# Solenoid_15.net
KiCad netlist of a schematic drawn in EAGLE
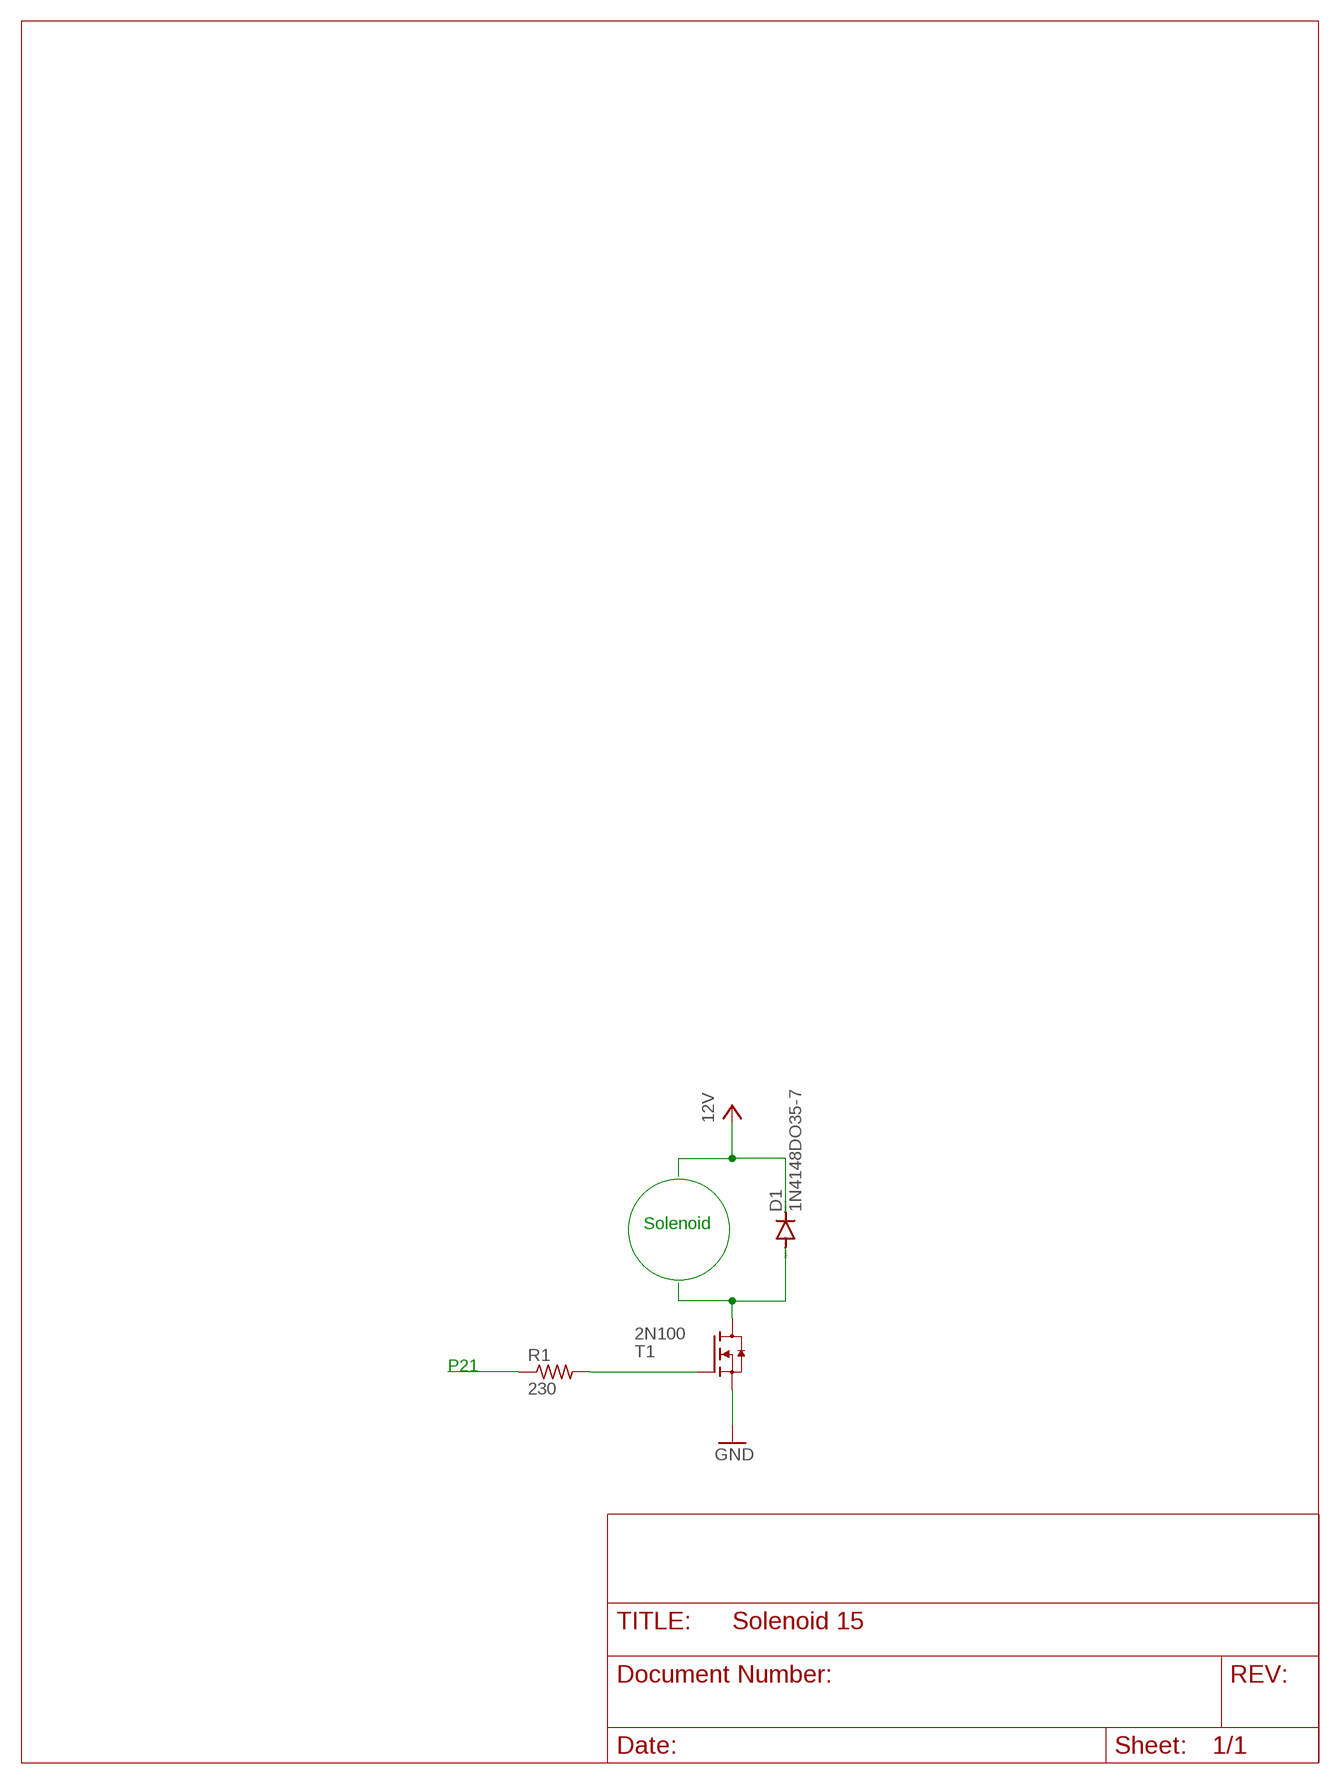
[diagram p0: schematic, sheet 1]

(export (version "E")
  (design (tool "Eeschema 10.0.6"))
  (components
    (comp (ref "D1")
      (value "1N4148DO35-7")
      (footprint "eagle-import:DO35-7")
      (libsource (lib "eagle-import") (part "1N4148DO35-7"))
    )
    (comp (ref "R1")
      (value "230")
      (footprint "eagle-import:0204_7")
      (libsource (lib "eagle-import") (part "R-US_0204/7"))
    )
    (comp (ref "T1")
      (value "2N100")
      (footprint "eagle-import:PG-TO263-7-3")
      (libsource (lib "eagle-import") (part "IPB180N06S4-H1"))
    )
  )
  (nets
    (net (code "1") (name "12V") (class "Default")
      (node (ref "D1") (pin "C") (pinfunction "C_C") (pintype "passive"))
    )
    (net (code "2") (name "GND") (class "Default")
      (node (ref "T1") (pin "2") (pinfunction "S_2") (pintype "passive"))
      (node (ref "T1") (pin "3") (pinfunction "S_3") (pintype "passive"))
      (node (ref "T1") (pin "5") (pinfunction "S_5") (pintype "passive"))
      (node (ref "T1") (pin "6") (pinfunction "S_6") (pintype "passive"))
      (node (ref "T1") (pin "7") (pinfunction "S_7") (pintype "passive"))
    )
    (net (code "3") (name "Net-(T1-D)") (class "Default")
      (node (ref "D1") (pin "A") (pinfunction "A_A") (pintype "passive"))
      (node (ref "T1") (pin "8") (pinfunction "D_8") (pintype "passive"))
    )
    (net (code "4") (name "Net-(T1-G)") (class "Default")
      (node (ref "R1") (pin "2") (pinfunction "2_2") (pintype "passive"))
      (node (ref "T1") (pin "1") (pinfunction "G_1") (pintype "passive"))
    )
    (net (code "5") (name "unconnected-(R1-Pad1)") (class "Default")
      (node (ref "R1") (pin "1") (pinfunction "1_1") (pintype "passive"))
    )
  )
)
